# CONSOLE.net
KiCad netlist of a schematic drawn in Altium Designer
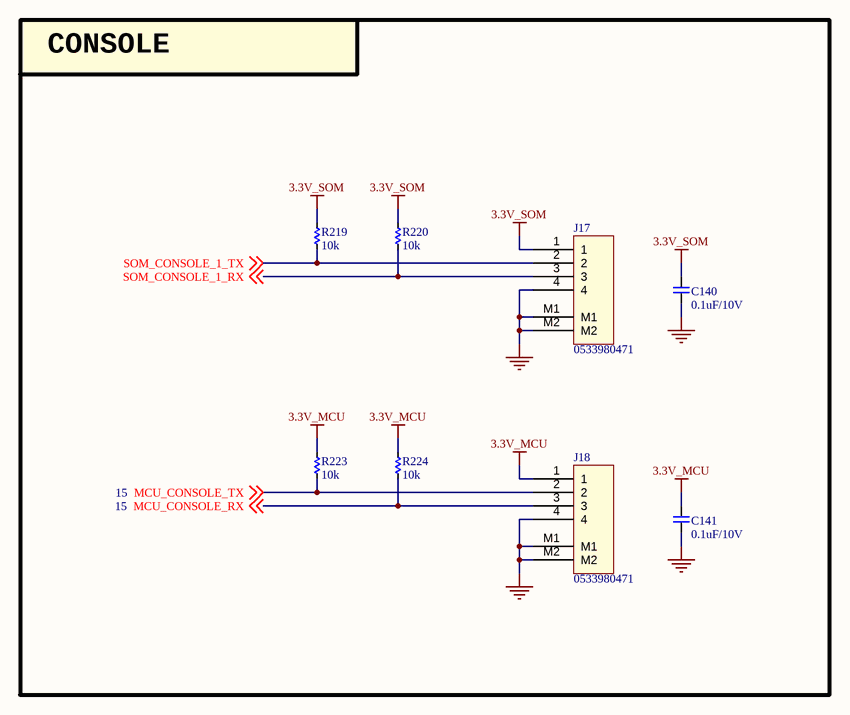
[diagram p0: CONSOLE.SchDoc]

(export (version "E")
  (design (tool "Eeschema 10.0.6"))
  (components
    (comp (ref "C140")
      (value "0.1uF/10V")
      (footprint "CAP_C_1005X60")
      (description "CAP CHIP")
      (libsource (lib "LABLIB") (part "_CAP_C_2"))
    )
    (comp (ref "C141")
      (value "0.1uF/10V")
      (footprint "CAP_C_1005X60")
      (description "CAP CHIP")
      (libsource (lib "LABLIB") (part "_CAP_C_2"))
    )
    (comp (ref "J17")
      (value "0533980471")
      (footprint "MOLEX_0533980471")
      (libsource (lib "LABLIB") (part "Header 4x1_2M"))
    )
    (comp (ref "J18")
      (value "0533980471")
      (footprint "MOLEX_0533980471")
      (libsource (lib "LABLIB") (part "Header 4x1_2M"))
    )
    (comp (ref "R219")
      (value "10k")
      (footprint "RES_C_1005X40")
      (description "RES")
      (libsource (lib "LABLIB") (part "_RES_B_2"))
    )
    (comp (ref "R220")
      (value "10k")
      (footprint "RES_C_1005X40")
      (description "RES")
      (libsource (lib "LABLIB") (part "_RES_B_2"))
    )
    (comp (ref "R223")
      (value "10k")
      (footprint "RES_C_1005X40")
      (description "RES")
      (libsource (lib "LABLIB") (part "_RES_B_2"))
    )
    (comp (ref "R224")
      (value "10k")
      (footprint "RES_C_1005X40")
      (description "RES")
      (libsource (lib "LABLIB") (part "_RES_B_2"))
    )
  )
  (nets
    (net (code "1") (name "3.3V_MCU") (class "Default")
      (node (ref "C141") (pin "2") (pinfunction "2_2") (pintype "passive"))
      (node (ref "J18") (pin "1") (pinfunction "1_1") (pintype "passive"))
      (node (ref "R223") (pin "2") (pinfunction "2_2") (pintype "passive"))
      (node (ref "R224") (pin "2") (pinfunction "2_2") (pintype "passive"))
    )
    (net (code "2") (name "3.3V_SOM") (class "Default")
      (node (ref "C140") (pin "2") (pinfunction "2_2") (pintype "passive"))
      (node (ref "J17") (pin "1") (pinfunction "1_1") (pintype "passive"))
      (node (ref "R219") (pin "2") (pinfunction "2_2") (pintype "passive"))
      (node (ref "R220") (pin "2") (pinfunction "2_2") (pintype "passive"))
    )
    (net (code "3") (name "GND") (class "Default")
      (node (ref "C140") (pin "1") (pinfunction "1_1") (pintype "passive"))
      (node (ref "C141") (pin "1") (pinfunction "1_1") (pintype "passive"))
      (node (ref "J17") (pin "4") (pinfunction "4_4") (pintype "passive"))
      (node (ref "J17") (pin "M1") (pinfunction "M1_M1") (pintype "passive"))
      (node (ref "J17") (pin "M2") (pinfunction "M2_M2") (pintype "passive"))
      (node (ref "J18") (pin "4") (pinfunction "4_4") (pintype "passive"))
      (node (ref "J18") (pin "M1") (pinfunction "M1_M1") (pintype "passive"))
      (node (ref "J18") (pin "M2") (pinfunction "M2_M2") (pintype "passive"))
    )
    (net (code "4") (name "MCU_CONSOLE_RX") (class "Default")
      (node (ref "J18") (pin "3") (pinfunction "3_3") (pintype "passive"))
      (node (ref "R224") (pin "1") (pinfunction "1_1") (pintype "passive"))
    )
    (net (code "5") (name "MCU_CONSOLE_TX") (class "Default")
      (node (ref "J18") (pin "2") (pinfunction "2_2") (pintype "passive"))
      (node (ref "R223") (pin "1") (pinfunction "1_1") (pintype "passive"))
    )
    (net (code "6") (name "SOM_CONSOLE_1_RX") (class "Default")
      (node (ref "J17") (pin "3") (pinfunction "3_3") (pintype "passive"))
      (node (ref "R220") (pin "1") (pinfunction "1_1") (pintype "passive"))
    )
    (net (code "7") (name "SOM_CONSOLE_1_TX") (class "Default")
      (node (ref "J17") (pin "2") (pinfunction "2_2") (pintype "passive"))
      (node (ref "R219") (pin "1") (pinfunction "1_1") (pintype "passive"))
    )
  )
)
